# ADC_Calibration.net
KiCad netlist of a schematic drawn in Altium Designer
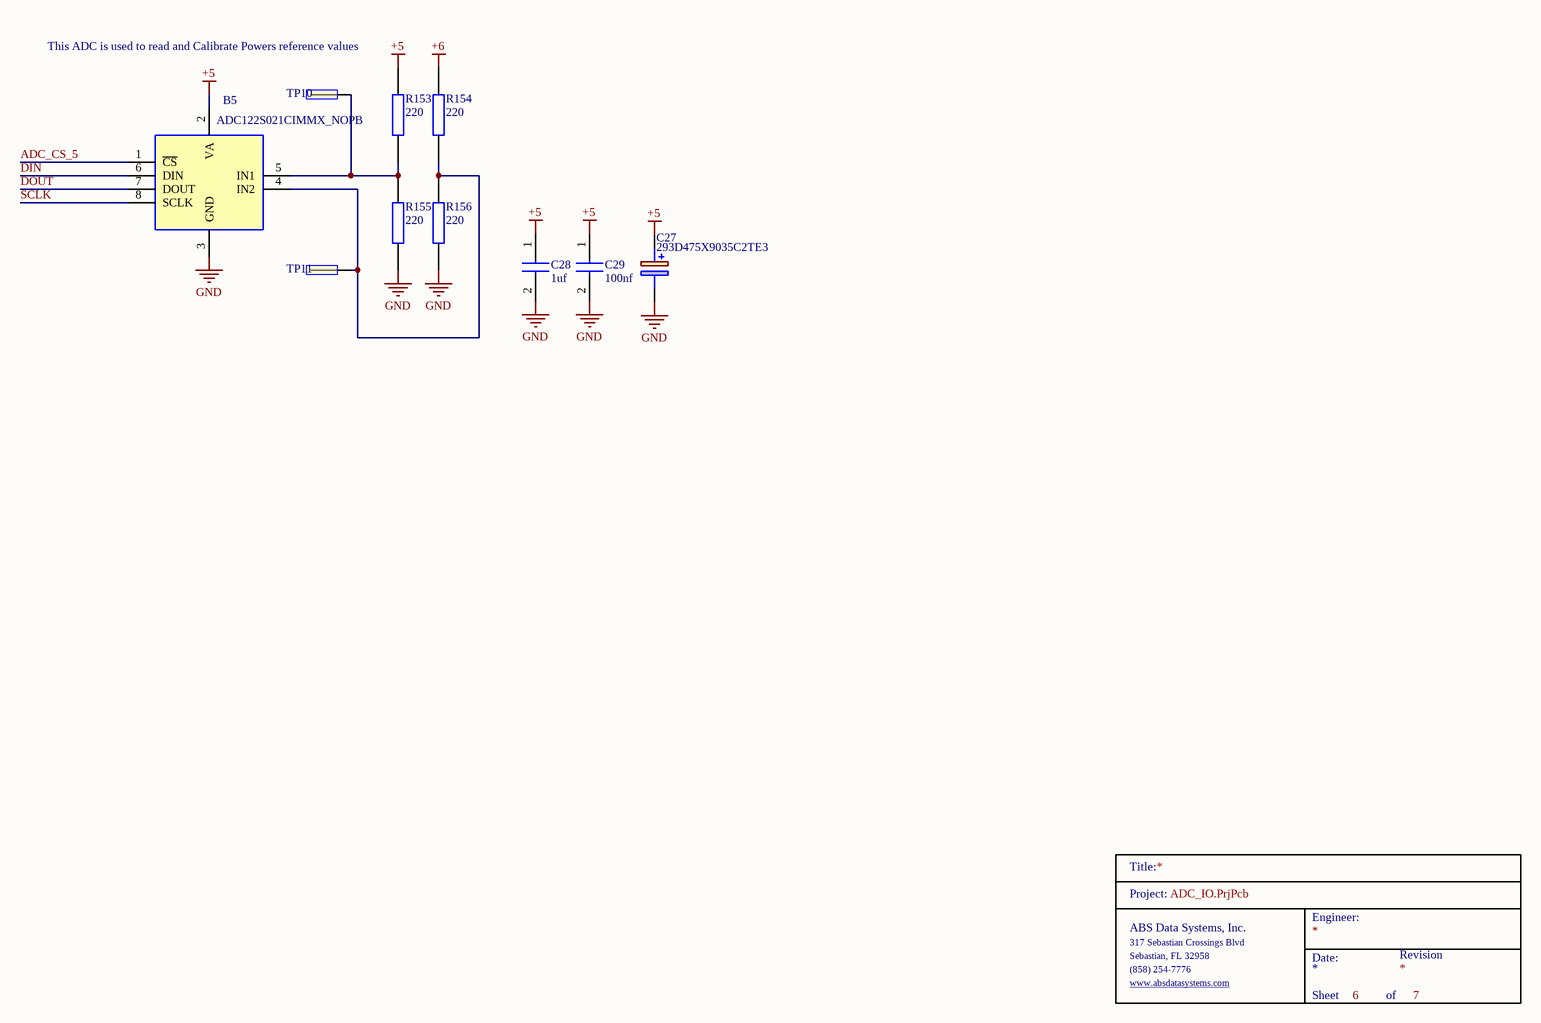
[diagram p0: ADC_Calibration.SchDoc]

(export (version "E")
  (design (tool "Eeschema 10.0.6"))
  (components
    (comp (ref "B5")
      (value "ADC122S021CIMMX_NOPB")
      (footprint "SOP65P490X110-8N")
      (description "2 Channel, 50 ksps to 200 ksps 12-Bit A/D Converter")
      (fields
        (field (name "MOUSER PART NUMBER") "926-A122S021CIMMXNPB")
        (field (name "MANUFACTURER_PART_NUMBER") "ADC122S021CIMMX/NOPB")
      )
      (libsource (lib "SemiConductors") (part "ADC122S021CIMMX_NOPB"))
    )
    (comp (ref "C27")
      (value "293D475X9035C2TE3")
      (footprint "CAPPM6032X280N")
      (fields (field (name "MOUSER PART NUMBER") "74-293D475X9035C2TE3"))
      (libsource (lib "Capacitors") (part "293D475X9035C2TE3"))
    )
    (comp (ref "C28")
      (value "1uf")
      (footprint "0603")
      (description "Samsung Electro-Mechanics 0603 1uf")
      (libsource (lib "Capacitors") (part "CL10B105KA8NNNL"))
    )
    (comp (ref "C29")
      (value "100nf")
      (footprint "0603")
      (description "Samsung Electro-Mechanics 0603 100nf")
      (libsource (lib "Capacitors") (part "CL10B104JB8NNNC"))
    )
    (comp (ref "R153")
      (value "220")
      (footprint "0603")
      (description "YAGEO 0603 220 ohm")
      (fields
        (field (name "MOUSER PART NUMBER") "603-RC0603JR-070RL")
        (field (name "MANUFACTURER_PART_NUMBER") "RC0603JR-070RL")
      )
      (libsource (lib "Resistors") (part "RC0603JR-07220RL"))
    )
    (comp (ref "R154")
      (value "220")
      (footprint "0603")
      (description "YAGEO 0603 220 ohm")
      (fields
        (field (name "MOUSER PART NUMBER") "603-RC0603JR-070RL")
        (field (name "MANUFACTURER_PART_NUMBER") "RC0603JR-070RL")
      )
      (libsource (lib "Resistors") (part "RC0603JR-07220RL"))
    )
    (comp (ref "R155")
      (value "220")
      (footprint "0603")
      (description "YAGEO 0603 220 ohm")
      (fields
        (field (name "MOUSER PART NUMBER") "603-RC0603JR-070RL")
        (field (name "MANUFACTURER_PART_NUMBER") "RC0603JR-070RL")
      )
      (libsource (lib "Resistors") (part "RC0603JR-07220RL"))
    )
    (comp (ref "R156")
      (value "220")
      (footprint "0603")
      (description "YAGEO 0603 220 ohm")
      (fields
        (field (name "MOUSER PART NUMBER") "603-RC0603JR-070RL")
        (field (name "MANUFACTURER_PART_NUMBER") "RC0603JR-070RL")
      )
      (libsource (lib "Resistors") (part "RC0603JR-07220RL"))
    )
    (comp (ref "TitleBlock_6") (value "TitleBlock") (libsource (lib "Misc") (part "TitleBlock")))
    (comp (ref "TP10")
      (value "TP")
      (footprint "TP")
      (fields
        (field (name "MANUFACTURER") "Samtec")
        (field (name "MANUFACTURER PART NUMBER") "TST-105-01-G-D")
      )
      (libsource (lib "Misc") (part "TP"))
    )
    (comp (ref "TP11")
      (value "TP")
      (footprint "TP")
      (fields
        (field (name "MANUFACTURER") "Samtec")
        (field (name "MANUFACTURER PART NUMBER") "TST-105-01-G-D")
      )
      (libsource (lib "Misc") (part "TP"))
    )
  )
  (nets
    (net (code "1") (name "+5") (class "Default")
      (node (ref "B5") (pin "2") (pinfunction "VA_2") (pintype "passive"))
      (node (ref "C27") (pin "1") (pinfunction "+_1") (pintype "passive"))
      (node (ref "C28") (pin "1") (pinfunction "1_1") (pintype "passive"))
      (node (ref "C29") (pin "1") (pinfunction "1_1") (pintype "passive"))
      (node (ref "R153") (pin "1") (pinfunction "1_1") (pintype "passive"))
    )
    (net (code "2") (name "+6") (class "Default")
      (node (ref "R154") (pin "2") (pinfunction "2_2") (pintype "passive"))
    )
    (net (code "3") (name "/ADC_CS_5") (class "Default")
      (node (ref "B5") (pin "1") (pinfunction "~{CS}_1") (pintype "passive"))
    )
    (net (code "4") (name "/DIN") (class "Default")
      (node (ref "B5") (pin "6") (pinfunction "DIN_6") (pintype "passive"))
    )
    (net (code "5") (name "/DOUT") (class "Default")
      (node (ref "B5") (pin "7") (pinfunction "DOUT_7") (pintype "passive"))
    )
    (net (code "6") (name "/SCLK") (class "Default")
      (node (ref "B5") (pin "8") (pinfunction "SCLK_8") (pintype "passive"))
    )
    (net (code "7") (name "GND") (class "Default")
      (node (ref "B5") (pin "3") (pinfunction "GND_3") (pintype "passive"))
      (node (ref "C27") (pin "2") (pinfunction "-_2") (pintype "passive"))
      (node (ref "C28") (pin "2") (pinfunction "2_2") (pintype "passive"))
      (node (ref "C29") (pin "2") (pinfunction "2_2") (pintype "passive"))
      (node (ref "R155") (pin "1") (pinfunction "1_1") (pintype "passive"))
      (node (ref "R156") (pin "2") (pinfunction "2_2") (pintype "passive"))
    )
    (net (code "8") (name "Net-(B5-IN1)") (class "Default")
      (node (ref "B5") (pin "5") (pinfunction "IN1_5") (pintype "passive"))
      (node (ref "R153") (pin "2") (pinfunction "2_2") (pintype "passive"))
      (node (ref "R155") (pin "2") (pinfunction "2_2") (pintype "passive"))
      (node (ref "TP10") (pin "1") (pinfunction "1_1") (pintype "passive"))
    )
    (net (code "9") (name "Net-(B5-IN2)") (class "Default")
      (node (ref "B5") (pin "4") (pinfunction "IN2_4") (pintype "passive"))
      (node (ref "R154") (pin "1") (pinfunction "1_1") (pintype "passive"))
      (node (ref "R156") (pin "1") (pinfunction "1_1") (pintype "passive"))
      (node (ref "TP11") (pin "1") (pinfunction "1_1") (pintype "passive"))
    )
  )
)
